# 12_-Valve-Control.net
KiCad netlist of a schematic drawn in Altium Designer
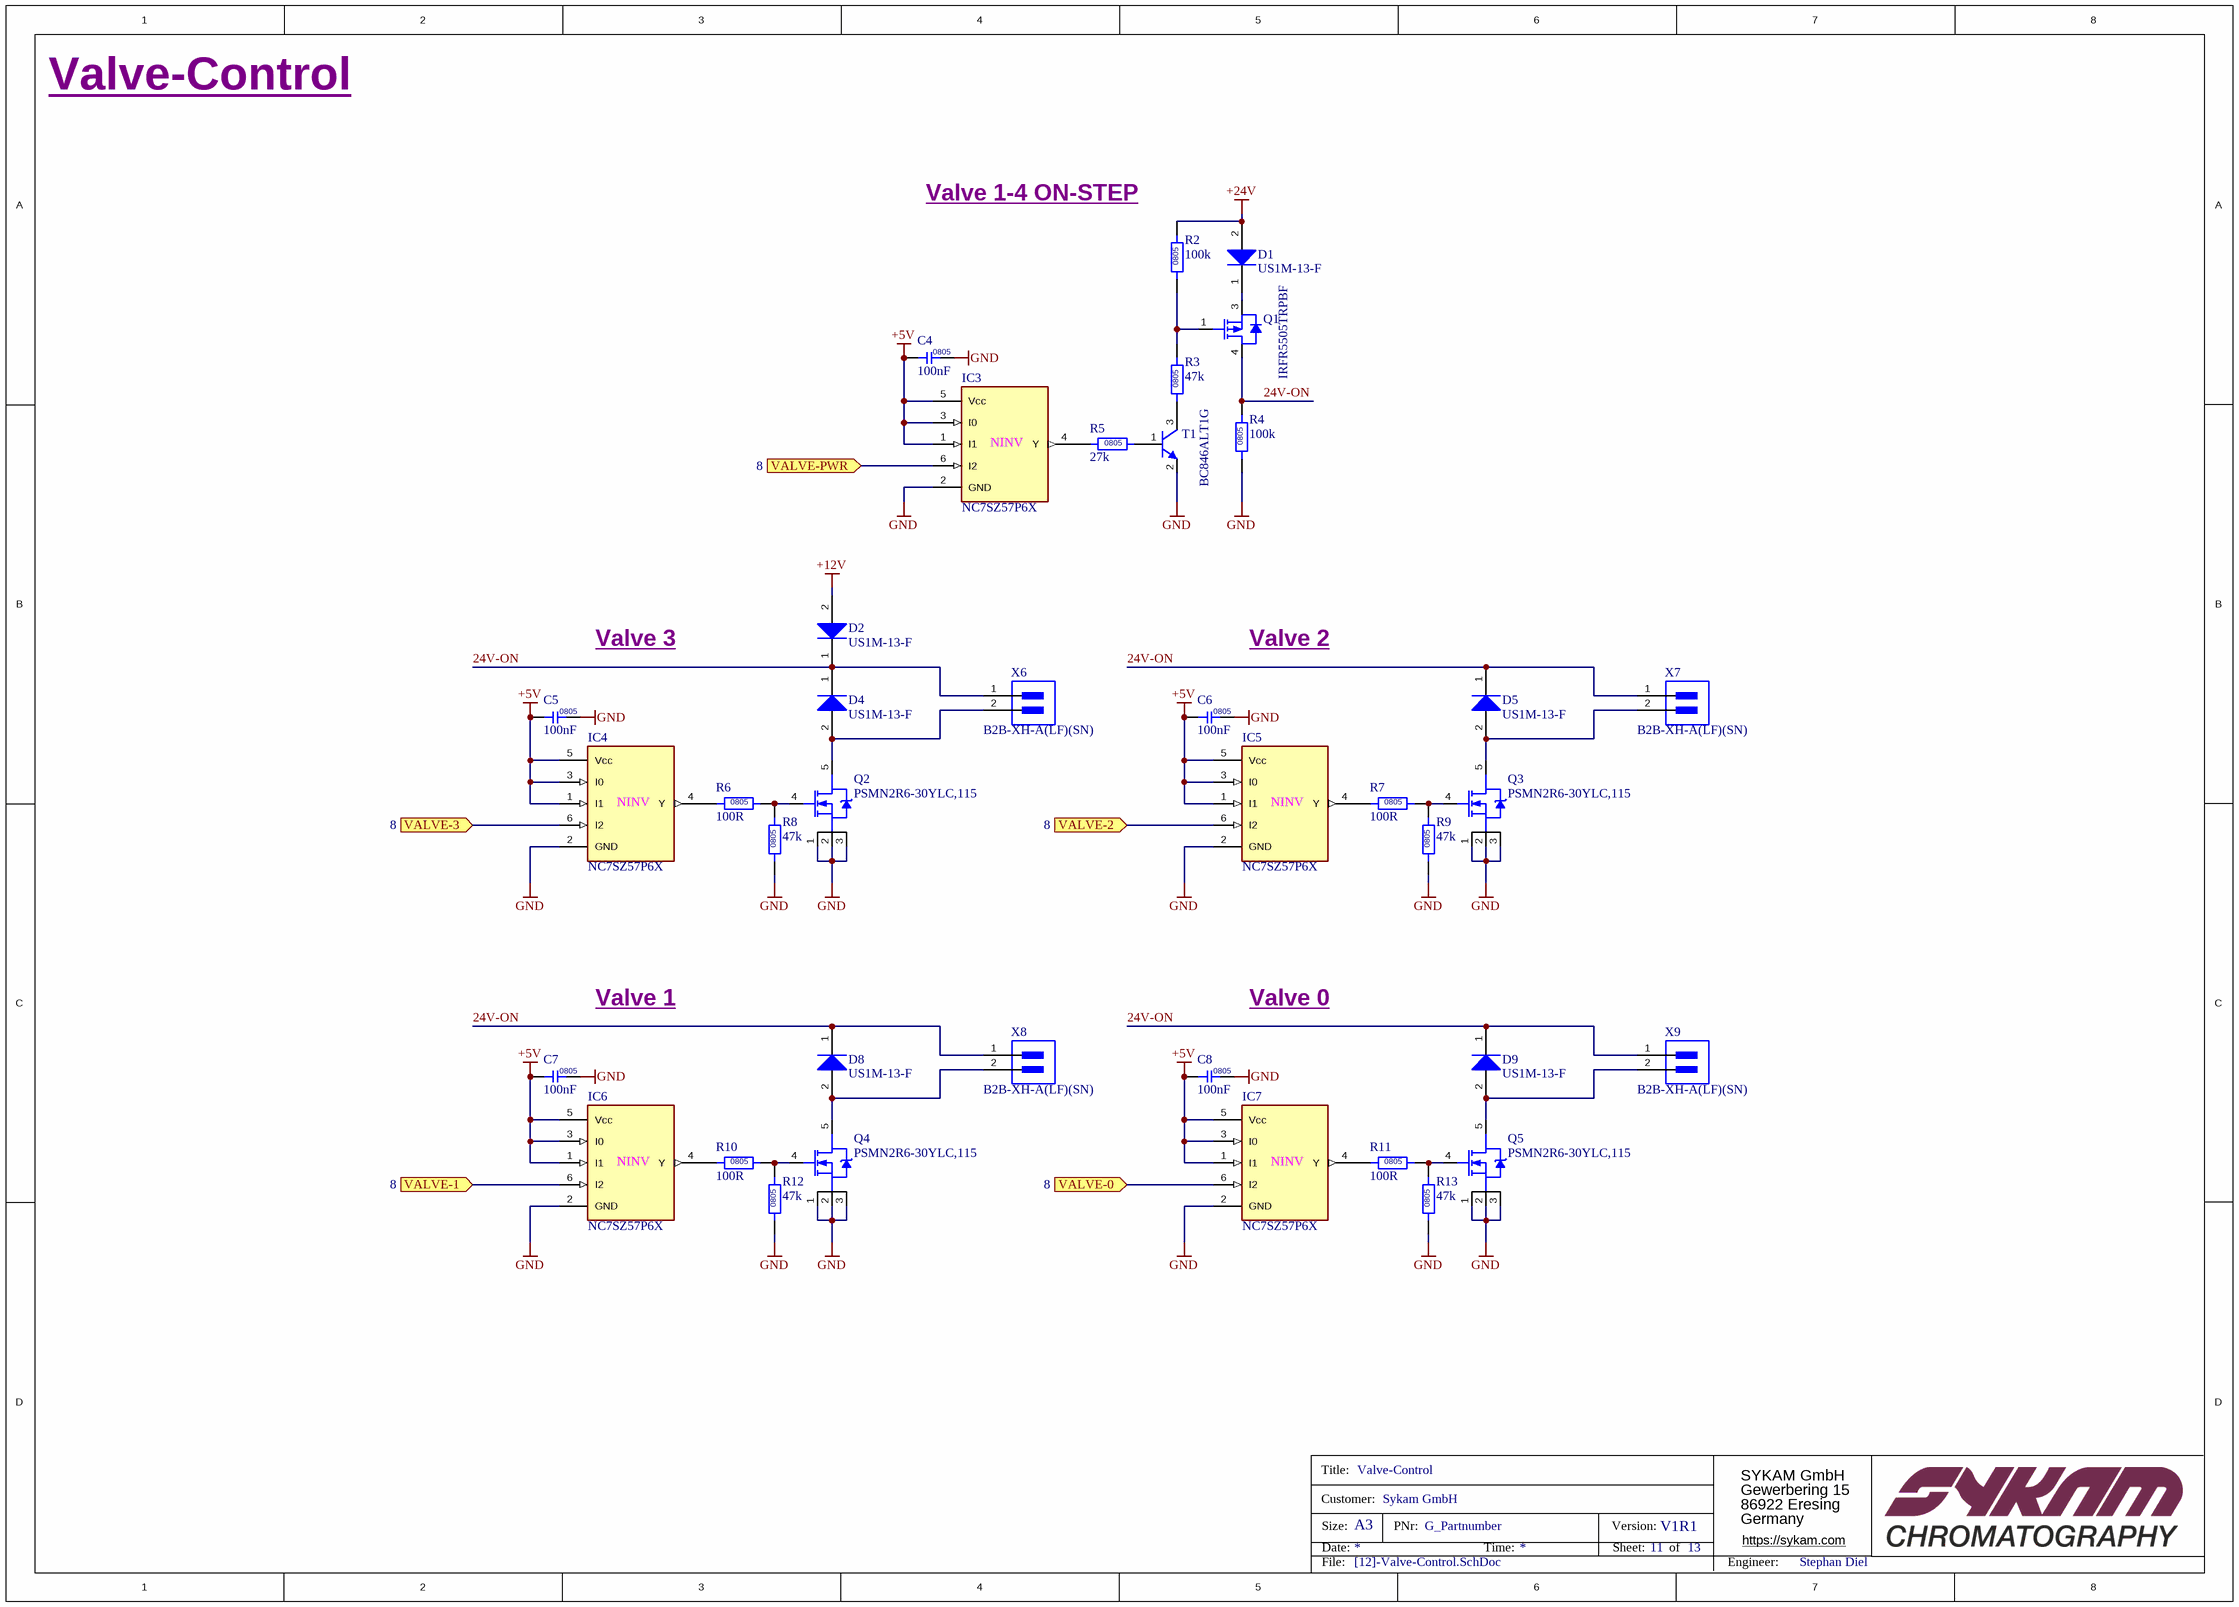
[diagram p0: [12]-Valve-Control.SchDoc]

(export (version "E")
  (design (tool "Eeschema 10.0.6"))
  (components
    (comp (ref "C4")
      (value "100nF")
      (footprint "C0805")
      (description "CAP CER 0.1UF 50V X7R 0805")
      (fields
        (field (name "MANUFACTURER PART NUMBER") "CC0805KRX7R9BB104")
        (field (name "TOLERANCE") "10%")
        (field (name "PCBCHECKED") "initials after Checked")
        (field (name "SCHCHECKED") "Initials after checked")
      )
      (libsource (lib "ToradexMainBoard-V0I1") (part "C_100nF_CC0805KRX7R9BB104"))
    )
    (comp (ref "C5")
      (value "100nF")
      (footprint "C0805")
      (description "CAP CER 0.1UF 50V X7R 0805")
      (fields
        (field (name "MANUFACTURER PART NUMBER") "CC0805KRX7R9BB104")
        (field (name "TOLERANCE") "10%")
        (field (name "PCBCHECKED") "initials after Checked")
        (field (name "SCHCHECKED") "Initials after checked")
      )
      (libsource (lib "ToradexMainBoard-V0I1") (part "C_100nF_CC0805KRX7R9BB104"))
    )
    (comp (ref "C6")
      (value "100nF")
      (footprint "C0805")
      (description "CAP CER 0.1UF 50V X7R 0805")
      (fields
        (field (name "MANUFACTURER PART NUMBER") "CC0805KRX7R9BB104")
        (field (name "TOLERANCE") "10%")
        (field (name "PCBCHECKED") "initials after Checked")
        (field (name "SCHCHECKED") "Initials after checked")
      )
      (libsource (lib "ToradexMainBoard-V0I1") (part "C_100nF_CC0805KRX7R9BB104"))
    )
    (comp (ref "C7")
      (value "100nF")
      (footprint "C0805")
      (description "CAP CER 0.1UF 50V X7R 0805")
      (fields
        (field (name "MANUFACTURER PART NUMBER") "CC0805KRX7R9BB104")
        (field (name "TOLERANCE") "10%")
        (field (name "PCBCHECKED") "initials after Checked")
        (field (name "SCHCHECKED") "Initials after checked")
      )
      (libsource (lib "ToradexMainBoard-V0I1") (part "C_100nF_CC0805KRX7R9BB104"))
    )
    (comp (ref "C8")
      (value "100nF")
      (footprint "C0805")
      (description "CAP CER 0.1UF 50V X7R 0805")
      (fields
        (field (name "MANUFACTURER PART NUMBER") "CC0805KRX7R9BB104")
        (field (name "TOLERANCE") "10%")
        (field (name "PCBCHECKED") "initials after Checked")
        (field (name "SCHCHECKED") "Initials after checked")
      )
      (libsource (lib "ToradexMainBoard-V0I1") (part "C_100nF_CC0805KRX7R9BB104"))
    )
    (comp (ref "D1")
      (value "US1M-13-F")
      (footprint "US1M-SMA-2_A_V")
      (description "Diode Switching 1KV 1A 2-Pin SMA T/R")
      (fields (field (name "MANUFACTURER") "Diodes"))
      (libsource (lib "ToradexMainBoard-V0I1") (part "D_US1M-13-F"))
    )
    (comp (ref "D2")
      (value "US1M-13-F")
      (footprint "US1M-SMA-2_A_V")
      (description "Diode Switching 1KV 1A 2-Pin SMA T/R")
      (fields (field (name "MANUFACTURER") "Diodes"))
      (libsource (lib "ToradexMainBoard-V0I1") (part "D_US1M-13-F"))
    )
    (comp (ref "D4")
      (value "US1M-13-F")
      (footprint "US1M-SMA-2_A_V")
      (description "Diode Switching 1KV 1A 2-Pin SMA T/R")
      (fields (field (name "MANUFACTURER") "Diodes"))
      (libsource (lib "ToradexMainBoard-V0I1") (part "D_US1M-13-F"))
    )
    (comp (ref "D5")
      (value "US1M-13-F")
      (footprint "US1M-SMA-2_A_V")
      (description "Diode Switching 1KV 1A 2-Pin SMA T/R")
      (fields (field (name "MANUFACTURER") "Diodes"))
      (libsource (lib "ToradexMainBoard-V0I1") (part "D_US1M-13-F"))
    )
    (comp (ref "D8")
      (value "US1M-13-F")
      (footprint "US1M-SMA-2_A_V")
      (description "Diode Switching 1KV 1A 2-Pin SMA T/R")
      (fields (field (name "MANUFACTURER") "Diodes"))
      (libsource (lib "ToradexMainBoard-V0I1") (part "D_US1M-13-F"))
    )
    (comp (ref "D9")
      (value "US1M-13-F")
      (footprint "US1M-SMA-2_A_V")
      (description "Diode Switching 1KV 1A 2-Pin SMA T/R")
      (fields (field (name "MANUFACTURER") "Diodes"))
      (libsource (lib "ToradexMainBoard-V0I1") (part "D_US1M-13-F"))
    )
    (comp (ref "IC3")
      (value "NC7SZ57P6X")
      (footprint "NC7SZ57P6X")
      (fields
        (field (name "MANUFACTURER") "ON Semiconductor / Fairchild")
        (field (name "PCBCHECKED") "initials after Checked")
        (field (name "SCHCHECKED") "Initials after checked")
      )
      (libsource (lib "ToradexMainBoard-V0I1") (part "IC_NC7SZ57P6X"))
    )
    (comp (ref "IC4")
      (value "NC7SZ57P6X")
      (footprint "NC7SZ57P6X")
      (fields
        (field (name "MANUFACTURER") "ON Semiconductor / Fairchild")
        (field (name "PCBCHECKED") "initials after Checked")
        (field (name "SCHCHECKED") "Initials after checked")
      )
      (libsource (lib "ToradexMainBoard-V0I1") (part "IC_NC7SZ57P6X"))
    )
    (comp (ref "IC5")
      (value "NC7SZ57P6X")
      (footprint "NC7SZ57P6X")
      (fields
        (field (name "MANUFACTURER") "ON Semiconductor / Fairchild")
        (field (name "PCBCHECKED") "initials after Checked")
        (field (name "SCHCHECKED") "Initials after checked")
      )
      (libsource (lib "ToradexMainBoard-V0I1") (part "IC_NC7SZ57P6X"))
    )
    (comp (ref "IC6")
      (value "NC7SZ57P6X")
      (footprint "NC7SZ57P6X")
      (fields
        (field (name "MANUFACTURER") "ON Semiconductor / Fairchild")
        (field (name "PCBCHECKED") "initials after Checked")
        (field (name "SCHCHECKED") "Initials after checked")
      )
      (libsource (lib "ToradexMainBoard-V0I1") (part "IC_NC7SZ57P6X"))
    )
    (comp (ref "IC7")
      (value "NC7SZ57P6X")
      (footprint "NC7SZ57P6X")
      (fields
        (field (name "MANUFACTURER") "ON Semiconductor / Fairchild")
        (field (name "PCBCHECKED") "initials after Checked")
        (field (name "SCHCHECKED") "Initials after checked")
      )
      (libsource (lib "ToradexMainBoard-V0I1") (part "IC_NC7SZ57P6X"))
    )
    (comp (ref "Q1")
      (value "IRFR5505TRPBF")
      (footprint "PMOS-DPak")
      (fields (field (name "MANUFACTURER") "International Rectifier"))
      (libsource (lib "ToradexMainBoard-V0I1") (part "Q_PMOS_IRFR5505TRPBF"))
    )
    (comp (ref "Q2")
      (value "PSMN2R6-30YLC,115")
      (footprint "PSMN2R6-LFPAK_SOT669")
      (description "PSMN2R6-30YLC - N-channel 30 V 2.8 mΩ logic level MOSFET in LFPAK using NextPower technology")
      (fields (field (name "MANUFACTURER") "Nexperia"))
      (libsource (lib "ToradexMainBoard-V0I1") (part "Q_NMOS_PSMN2R6-30YLC,115"))
    )
    (comp (ref "Q3")
      (value "PSMN2R6-30YLC,115")
      (footprint "PSMN2R6-LFPAK_SOT669")
      (description "PSMN2R6-30YLC - N-channel 30 V 2.8 mΩ logic level MOSFET in LFPAK using NextPower technology")
      (fields (field (name "MANUFACTURER") "Nexperia"))
      (libsource (lib "ToradexMainBoard-V0I1") (part "Q_NMOS_PSMN2R6-30YLC,115"))
    )
    (comp (ref "Q4")
      (value "PSMN2R6-30YLC,115")
      (footprint "PSMN2R6-LFPAK_SOT669")
      (description "PSMN2R6-30YLC - N-channel 30 V 2.8 mΩ logic level MOSFET in LFPAK using NextPower technology")
      (fields (field (name "MANUFACTURER") "Nexperia"))
      (libsource (lib "ToradexMainBoard-V0I1") (part "Q_NMOS_PSMN2R6-30YLC,115"))
    )
    (comp (ref "Q5")
      (value "PSMN2R6-30YLC,115")
      (footprint "PSMN2R6-LFPAK_SOT669")
      (description "PSMN2R6-30YLC - N-channel 30 V 2.8 mΩ logic level MOSFET in LFPAK using NextPower technology")
      (fields (field (name "MANUFACTURER") "Nexperia"))
      (libsource (lib "ToradexMainBoard-V0I1") (part "Q_NMOS_PSMN2R6-30YLC,115"))
    )
    (comp (ref "R2")
      (value "100k")
      (footprint "R0805")
      (description "RES SMD 100K OHM 1% 1/8W 0805")
      (fields
        (field (name "MANUFACTURER PART NUMBER") "RC0805FR-07100KL")
        (field (name "TOLERANCE") "1%")
        (field (name "PCBCHECKED") "initials after Checked")
        (field (name "SCHCHECKED") "Initials after checked")
      )
      (libsource (lib "ToradexMainBoard-V0I1") (part "R_100k_RC0805FR-07100KL"))
    )
    (comp (ref "R3")
      (value "47k")
      (footprint "R0805")
      (description "SMD Resistor, Thick film 47 kOhm,  ±  1 %, 0805, CRCW080547K0FKEA, Vishay")
      (fields
        (field (name "MANUFACTURER") "Vishay")
        (field (name "MANUFACTURER PART NUMBER") "CRCW080547K0FKEA")
      )
      (libsource (lib "ToradexMainBoard-V0I1") (part "R_47k_CRCW080547K0FKEA"))
    )
    (comp (ref "R4")
      (value "100k")
      (footprint "R0805")
      (description "RES SMD 100K OHM 1% 1/8W 0805")
      (fields
        (field (name "MANUFACTURER PART NUMBER") "RC0805FR-07100KL")
        (field (name "TOLERANCE") "1%")
        (field (name "PCBCHECKED") "initials after Checked")
        (field (name "SCHCHECKED") "Initials after checked")
      )
      (libsource (lib "ToradexMainBoard-V0I1") (part "R_100k_RC0805FR-07100KL"))
    )
    (comp (ref "R5")
      (value "27k")
      (footprint "R0805")
      (description "Surface Mount Thick Film Resistor, RC Series, 27 kohm, 125 mW, - 1%, 150 V, 0805 [2012 Metric]")
      (fields
        (field (name "MANUFACTURER") "Yageo")
        (field (name "MANUFACTURER PART NUMBER") "RC0805FR-0727KL")
      )
      (libsource (lib "ToradexMainBoard-V0I1") (part "R_27k_RC0805FR-0727KL"))
    )
    (comp (ref "R6")
      (value "100R")
      (footprint "R0805")
      (description "Res Thick Film 0805 100 Ohm 1% 0.125W(1/8W) ±100ppm/C Epoxy SMD T/R")
      (fields
        (field (name "MANUFACTURER") "Yageo")
        (field (name "MANUFACTURER PART NUMBER") "RC0805FR-07100RL")
      )
      (libsource (lib "ToradexMainBoard-V0I1") (part "R_100R_RC0805FR-07100RL"))
    )
    (comp (ref "R7")
      (value "100R")
      (footprint "R0805")
      (description "Res Thick Film 0805 100 Ohm 1% 0.125W(1/8W) ±100ppm/C Epoxy SMD T/R")
      (fields
        (field (name "MANUFACTURER") "Yageo")
        (field (name "MANUFACTURER PART NUMBER") "RC0805FR-07100RL")
      )
      (libsource (lib "ToradexMainBoard-V0I1") (part "R_100R_RC0805FR-07100RL"))
    )
    (comp (ref "R8")
      (value "47k")
      (footprint "R0805")
      (description "SMD Resistor, Thick film 47 kOhm,  ±  1 %, 0805, CRCW080547K0FKEA, Vishay")
      (fields
        (field (name "MANUFACTURER") "Vishay")
        (field (name "MANUFACTURER PART NUMBER") "CRCW080547K0FKEA")
      )
      (libsource (lib "ToradexMainBoard-V0I1") (part "R_47k_CRCW080547K0FKEA"))
    )
    (comp (ref "R9")
      (value "47k")
      (footprint "R0805")
      (description "SMD Resistor, Thick film 47 kOhm,  ±  1 %, 0805, CRCW080547K0FKEA, Vishay")
      (fields
        (field (name "MANUFACTURER") "Vishay")
        (field (name "MANUFACTURER PART NUMBER") "CRCW080547K0FKEA")
      )
      (libsource (lib "ToradexMainBoard-V0I1") (part "R_47k_CRCW080547K0FKEA"))
    )
    (comp (ref "R10")
      (value "100R")
      (footprint "R0805")
      (description "Res Thick Film 0805 100 Ohm 1% 0.125W(1/8W) ±100ppm/C Epoxy SMD T/R")
      (fields
        (field (name "MANUFACTURER") "Yageo")
        (field (name "MANUFACTURER PART NUMBER") "RC0805FR-07100RL")
      )
      (libsource (lib "ToradexMainBoard-V0I1") (part "R_100R_RC0805FR-07100RL"))
    )
    (comp (ref "R11")
      (value "100R")
      (footprint "R0805")
      (description "Res Thick Film 0805 100 Ohm 1% 0.125W(1/8W) ±100ppm/C Epoxy SMD T/R")
      (fields
        (field (name "MANUFACTURER") "Yageo")
        (field (name "MANUFACTURER PART NUMBER") "RC0805FR-07100RL")
      )
      (libsource (lib "ToradexMainBoard-V0I1") (part "R_100R_RC0805FR-07100RL"))
    )
    (comp (ref "R12")
      (value "47k")
      (footprint "R0805")
      (description "SMD Resistor, Thick film 47 kOhm,  ±  1 %, 0805, CRCW080547K0FKEA, Vishay")
      (fields
        (field (name "MANUFACTURER") "Vishay")
        (field (name "MANUFACTURER PART NUMBER") "CRCW080547K0FKEA")
      )
      (libsource (lib "ToradexMainBoard-V0I1") (part "R_47k_CRCW080547K0FKEA"))
    )
    (comp (ref "R13")
      (value "47k")
      (footprint "R0805")
      (description "SMD Resistor, Thick film 47 kOhm,  ±  1 %, 0805, CRCW080547K0FKEA, Vishay")
      (fields
        (field (name "MANUFACTURER") "Vishay")
        (field (name "MANUFACTURER PART NUMBER") "CRCW080547K0FKEA")
      )
      (libsource (lib "ToradexMainBoard-V0I1") (part "R_47k_CRCW080547K0FKEA"))
    )
    (comp (ref "T1")
      (value "BC846ALT1G")
      (footprint "ONSC-SOT-23-3-318-08_V")
      (description "ON SEMICONDUCTOR - BC846ALT1G - BIPOLAR TRANSISTOR, FULL REEL")
      (fields (field (name "MANUFACTURER") "ON Semiconductor"))
      (libsource (lib "ToradexMainBoard-V0I1") (part "T_BC846ALT1G"))
    )
    (comp (ref "X6")
      (value "B2B-XH-A(LF)(SN)")
      (footprint "CON_2p_JST-B2B-XH-A_V")
      (description "Conn Shrouded Header (4 Sides) HDR 2 POS 2.5mm Solder ST Thru-Hole Box")
      (fields (field (name "MANUFACTURER") "JST"))
      (libsource (lib "ToradexMainBoard-V0I1") (part "CON_2p_B2B-XH-A(LF)(SN)"))
    )
    (comp (ref "X7")
      (value "B2B-XH-A(LF)(SN)")
      (footprint "CON_2p_JST-B2B-XH-A_V")
      (description "Conn Shrouded Header (4 Sides) HDR 2 POS 2.5mm Solder ST Thru-Hole Box")
      (fields (field (name "MANUFACTURER") "JST"))
      (libsource (lib "ToradexMainBoard-V0I1") (part "CON_2p_B2B-XH-A(LF)(SN)"))
    )
    (comp (ref "X8")
      (value "B2B-XH-A(LF)(SN)")
      (footprint "CON_2p_JST-B2B-XH-A_V")
      (description "Conn Shrouded Header (4 Sides) HDR 2 POS 2.5mm Solder ST Thru-Hole Box")
      (fields (field (name "MANUFACTURER") "JST"))
      (libsource (lib "ToradexMainBoard-V0I1") (part "CON_2p_B2B-XH-A(LF)(SN)"))
    )
    (comp (ref "X9")
      (value "B2B-XH-A(LF)(SN)")
      (footprint "CON_2p_JST-B2B-XH-A_V")
      (description "Conn Shrouded Header (4 Sides) HDR 2 POS 2.5mm Solder ST Thru-Hole Box")
      (fields (field (name "MANUFACTURER") "JST"))
      (libsource (lib "ToradexMainBoard-V0I1") (part "CON_2p_B2B-XH-A(LF)(SN)"))
    )
  )
  (nets
    (net (code "1") (name "+5V") (class "Default")
      (node (ref "C4") (pin "1") (pinfunction "1_1") (pintype "passive"))
      (node (ref "C5") (pin "1") (pinfunction "1_1") (pintype "passive"))
      (node (ref "C6") (pin "1") (pinfunction "1_1") (pintype "passive"))
      (node (ref "C7") (pin "1") (pinfunction "1_1") (pintype "passive"))
      (node (ref "C8") (pin "1") (pinfunction "1_1") (pintype "passive"))
      (node (ref "IC3") (pin "1") (pinfunction "I1_1") (pintype "input"))
      (node (ref "IC3") (pin "3") (pinfunction "I0_3") (pintype "input"))
      (node (ref "IC3") (pin "5") (pinfunction "Vcc_5") (pintype "passive"))
      (node (ref "IC4") (pin "1") (pinfunction "I1_1") (pintype "input"))
      (node (ref "IC4") (pin "3") (pinfunction "I0_3") (pintype "input"))
      (node (ref "IC4") (pin "5") (pinfunction "Vcc_5") (pintype "passive"))
      (node (ref "IC5") (pin "1") (pinfunction "I1_1") (pintype "input"))
      (node (ref "IC5") (pin "3") (pinfunction "I0_3") (pintype "input"))
      (node (ref "IC5") (pin "5") (pinfunction "Vcc_5") (pintype "passive"))
      (node (ref "IC6") (pin "1") (pinfunction "I1_1") (pintype "input"))
      (node (ref "IC6") (pin "3") (pinfunction "I0_3") (pintype "input"))
      (node (ref "IC6") (pin "5") (pinfunction "Vcc_5") (pintype "passive"))
      (node (ref "IC7") (pin "1") (pinfunction "I1_1") (pintype "input"))
      (node (ref "IC7") (pin "3") (pinfunction "I0_3") (pintype "input"))
      (node (ref "IC7") (pin "5") (pinfunction "Vcc_5") (pintype "passive"))
    )
    (net (code "2") (name "+12V") (class "Default")
      (node (ref "D2") (pin "2") (pinfunction "K_2") (pintype "passive"))
    )
    (net (code "3") (name "+24V") (class "Default")
      (node (ref "D1") (pin "2") (pinfunction "K_2") (pintype "passive"))
      (node (ref "R2") (pin "2") (pinfunction "2_2") (pintype "passive"))
    )
    (net (code "4") (name "/24V-ON") (class "Default")
      (node (ref "D2") (pin "1") (pinfunction "A_1") (pintype "passive"))
      (node (ref "D4") (pin "1") (pinfunction "A_1") (pintype "passive"))
      (node (ref "D5") (pin "1") (pinfunction "A_1") (pintype "passive"))
      (node (ref "D8") (pin "1") (pinfunction "A_1") (pintype "passive"))
      (node (ref "D9") (pin "1") (pinfunction "A_1") (pintype "passive"))
      (node (ref "Q1") (pin "4") (pinfunction "D_4") (pintype "passive"))
      (node (ref "R4") (pin "2") (pinfunction "2_2") (pintype "passive"))
      (node (ref "X6") (pin "1") (pintype "passive"))
      (node (ref "X7") (pin "1") (pintype "passive"))
      (node (ref "X8") (pin "1") (pintype "passive"))
      (node (ref "X9") (pin "1") (pintype "passive"))
    )
    (net (code "5") (name "/VALVE-0") (class "Default")
      (node (ref "IC7") (pin "6") (pinfunction "I2_6") (pintype "input"))
    )
    (net (code "6") (name "/VALVE-1") (class "Default")
      (node (ref "IC6") (pin "6") (pinfunction "I2_6") (pintype "input"))
    )
    (net (code "7") (name "/VALVE-2") (class "Default")
      (node (ref "IC5") (pin "6") (pinfunction "I2_6") (pintype "input"))
    )
    (net (code "8") (name "/VALVE-3") (class "Default")
      (node (ref "IC4") (pin "6") (pinfunction "I2_6") (pintype "input"))
    )
    (net (code "9") (name "/VALVE-PWR") (class "Default")
      (node (ref "IC3") (pin "6") (pinfunction "I2_6") (pintype "input"))
    )
    (net (code "10") (name "GND") (class "Default")
      (node (ref "C4") (pin "2") (pinfunction "2_2") (pintype "passive"))
      (node (ref "C5") (pin "2") (pinfunction "2_2") (pintype "passive"))
      (node (ref "C6") (pin "2") (pinfunction "2_2") (pintype "passive"))
      (node (ref "C7") (pin "2") (pinfunction "2_2") (pintype "passive"))
      (node (ref "C8") (pin "2") (pinfunction "2_2") (pintype "passive"))
      (node (ref "IC3") (pin "2") (pinfunction "GND_2") (pintype "passive"))
      (node (ref "IC4") (pin "2") (pinfunction "GND_2") (pintype "passive"))
      (node (ref "IC5") (pin "2") (pinfunction "GND_2") (pintype "passive"))
      (node (ref "IC6") (pin "2") (pinfunction "GND_2") (pintype "passive"))
      (node (ref "IC7") (pin "2") (pinfunction "GND_2") (pintype "passive"))
      (node (ref "Q2") (pin "1") (pinfunction "D_1") (pintype "passive"))
      (node (ref "Q2") (pin "2") (pinfunction "D_2") (pintype "passive"))
      (node (ref "Q2") (pin "3") (pinfunction "D_3") (pintype "passive"))
      (node (ref "Q3") (pin "1") (pinfunction "D_1") (pintype "passive"))
      (node (ref "Q3") (pin "2") (pinfunction "D_2") (pintype "passive"))
      (node (ref "Q3") (pin "3") (pinfunction "D_3") (pintype "passive"))
      (node (ref "Q4") (pin "1") (pinfunction "D_1") (pintype "passive"))
      (node (ref "Q4") (pin "2") (pinfunction "D_2") (pintype "passive"))
      (node (ref "Q4") (pin "3") (pinfunction "D_3") (pintype "passive"))
      (node (ref "Q5") (pin "1") (pinfunction "D_1") (pintype "passive"))
      (node (ref "Q5") (pin "2") (pinfunction "D_2") (pintype "passive"))
      (node (ref "Q5") (pin "3") (pinfunction "D_3") (pintype "passive"))
      (node (ref "R12") (pin "1") (pinfunction "1_1") (pintype "passive"))
      (node (ref "R13") (pin "1") (pinfunction "1_1") (pintype "passive"))
      (node (ref "R4") (pin "1") (pinfunction "1_1") (pintype "passive"))
      (node (ref "R8") (pin "1") (pinfunction "1_1") (pintype "passive"))
      (node (ref "R9") (pin "1") (pinfunction "1_1") (pintype "passive"))
      (node (ref "T1") (pin "2") (pinfunction "E_2") (pintype "passive"))
    )
    (net (code "11") (name "Net-(D1-A)") (class "Default")
      (node (ref "D1") (pin "1") (pinfunction "A_1") (pintype "passive"))
      (node (ref "Q1") (pin "3") (pinfunction "S_3") (pintype "passive"))
    )
    (net (code "12") (name "Net-(D4-K)") (class "Default")
      (node (ref "D4") (pin "2") (pinfunction "K_2") (pintype "passive"))
      (node (ref "Q2") (pin "5") (pinfunction "D_5") (pintype "passive"))
      (node (ref "X6") (pin "2") (pintype "passive"))
    )
    (net (code "13") (name "Net-(D5-K)") (class "Default")
      (node (ref "D5") (pin "2") (pinfunction "K_2") (pintype "passive"))
      (node (ref "Q3") (pin "5") (pinfunction "D_5") (pintype "passive"))
      (node (ref "X7") (pin "2") (pintype "passive"))
    )
    (net (code "14") (name "Net-(D8-K)") (class "Default")
      (node (ref "D8") (pin "2") (pinfunction "K_2") (pintype "passive"))
      (node (ref "Q4") (pin "5") (pinfunction "D_5") (pintype "passive"))
      (node (ref "X8") (pin "2") (pintype "passive"))
    )
    (net (code "15") (name "Net-(D9-K)") (class "Default")
      (node (ref "D9") (pin "2") (pinfunction "K_2") (pintype "passive"))
      (node (ref "Q5") (pin "5") (pinfunction "D_5") (pintype "passive"))
      (node (ref "X9") (pin "2") (pintype "passive"))
    )
    (net (code "16") (name "Net-(IC3-Y)") (class "Default")
      (node (ref "IC3") (pin "4") (pinfunction "Y_4") (pintype "output"))
      (node (ref "R5") (pin "1") (pinfunction "1_1") (pintype "passive"))
    )
    (net (code "17") (name "Net-(IC4-Y)") (class "Default")
      (node (ref "IC4") (pin "4") (pinfunction "Y_4") (pintype "output"))
      (node (ref "R6") (pin "1") (pinfunction "1_1") (pintype "passive"))
    )
    (net (code "18") (name "Net-(IC5-Y)") (class "Default")
      (node (ref "IC5") (pin "4") (pinfunction "Y_4") (pintype "output"))
      (node (ref "R7") (pin "1") (pinfunction "1_1") (pintype "passive"))
    )
    (net (code "19") (name "Net-(IC6-Y)") (class "Default")
      (node (ref "IC6") (pin "4") (pinfunction "Y_4") (pintype "output"))
      (node (ref "R10") (pin "1") (pinfunction "1_1") (pintype "passive"))
    )
    (net (code "20") (name "Net-(IC7-Y)") (class "Default")
      (node (ref "IC7") (pin "4") (pinfunction "Y_4") (pintype "output"))
      (node (ref "R11") (pin "1") (pinfunction "1_1") (pintype "passive"))
    )
    (net (code "21") (name "Net-(Q1-G)") (class "Default")
      (node (ref "Q1") (pin "1") (pinfunction "G_1") (pintype "passive"))
      (node (ref "R2") (pin "1") (pinfunction "1_1") (pintype "passive"))
      (node (ref "R3") (pin "2") (pinfunction "2_2") (pintype "passive"))
    )
    (net (code "22") (name "Net-(Q2-G)") (class "Default")
      (node (ref "Q2") (pin "4") (pinfunction "G_4") (pintype "passive"))
      (node (ref "R6") (pin "2") (pinfunction "2_2") (pintype "passive"))
      (node (ref "R8") (pin "2") (pinfunction "2_2") (pintype "passive"))
    )
    (net (code "23") (name "Net-(Q3-G)") (class "Default")
      (node (ref "Q3") (pin "4") (pinfunction "G_4") (pintype "passive"))
      (node (ref "R7") (pin "2") (pinfunction "2_2") (pintype "passive"))
      (node (ref "R9") (pin "2") (pinfunction "2_2") (pintype "passive"))
    )
    (net (code "24") (name "Net-(Q4-G)") (class "Default")
      (node (ref "Q4") (pin "4") (pinfunction "G_4") (pintype "passive"))
      (node (ref "R10") (pin "2") (pinfunction "2_2") (pintype "passive"))
      (node (ref "R12") (pin "2") (pinfunction "2_2") (pintype "passive"))
    )
    (net (code "25") (name "Net-(Q5-G)") (class "Default")
      (node (ref "Q5") (pin "4") (pinfunction "G_4") (pintype "passive"))
      (node (ref "R11") (pin "2") (pinfunction "2_2") (pintype "passive"))
      (node (ref "R13") (pin "2") (pinfunction "2_2") (pintype "passive"))
    )
    (net (code "26") (name "Net-(T1-B)") (class "Default")
      (node (ref "R5") (pin "2") (pinfunction "2_2") (pintype "passive"))
      (node (ref "T1") (pin "1") (pinfunction "B_1") (pintype "passive"))
    )
    (net (code "27") (name "Net-(T1-C)") (class "Default")
      (node (ref "R3") (pin "1") (pinfunction "1_1") (pintype "passive"))
      (node (ref "T1") (pin "3") (pinfunction "C_3") (pintype "passive"))
    )
  )
)
